# TSOC_PSoC4L.net
KiCad netlist of a schematic drawn in EAGLE
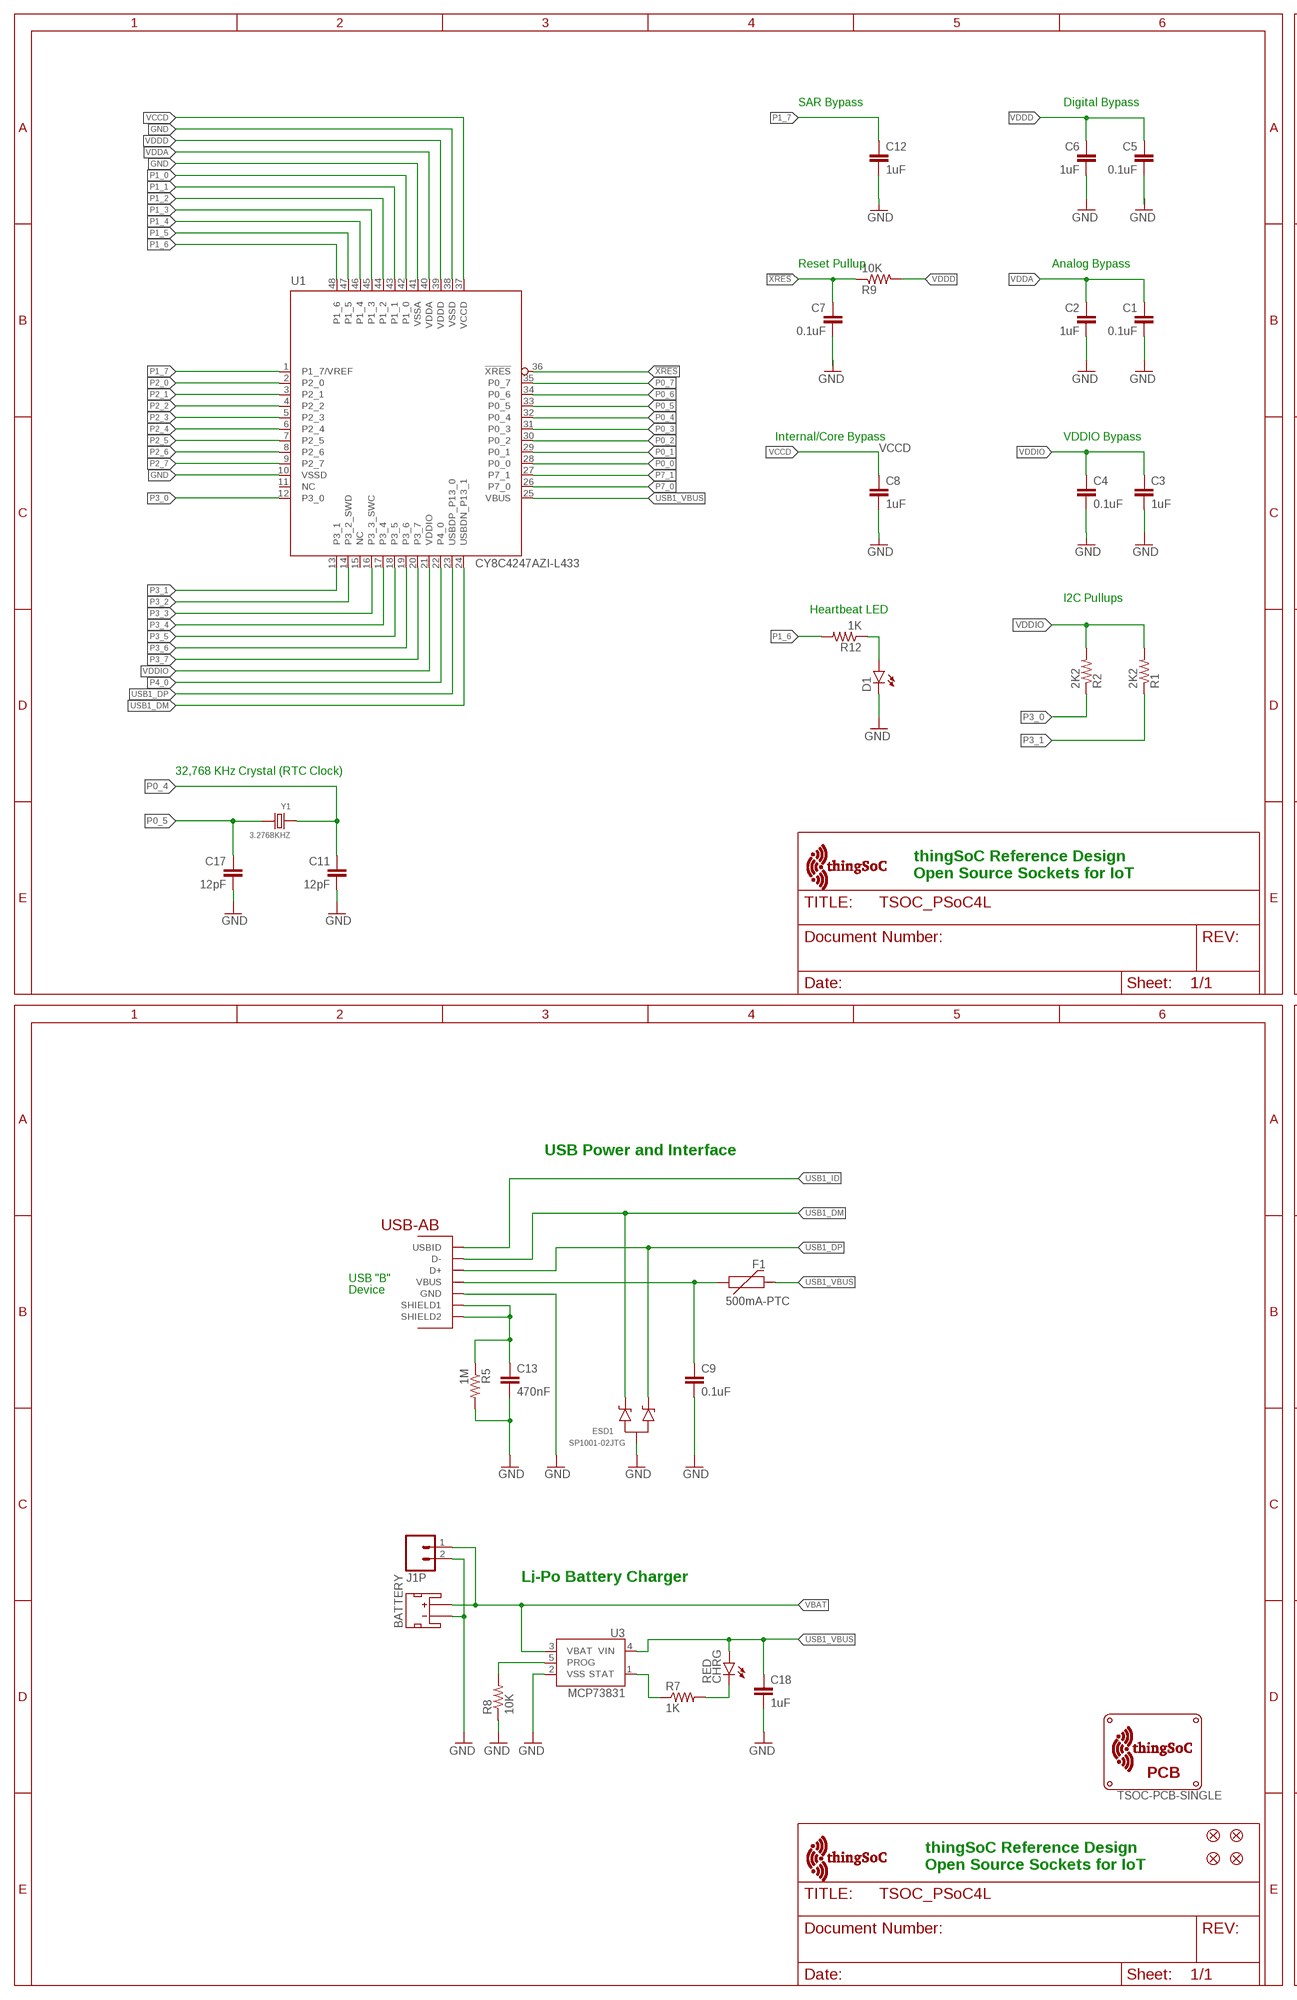
[diagram p0: schematic, sheet 1, part 1 of 2]
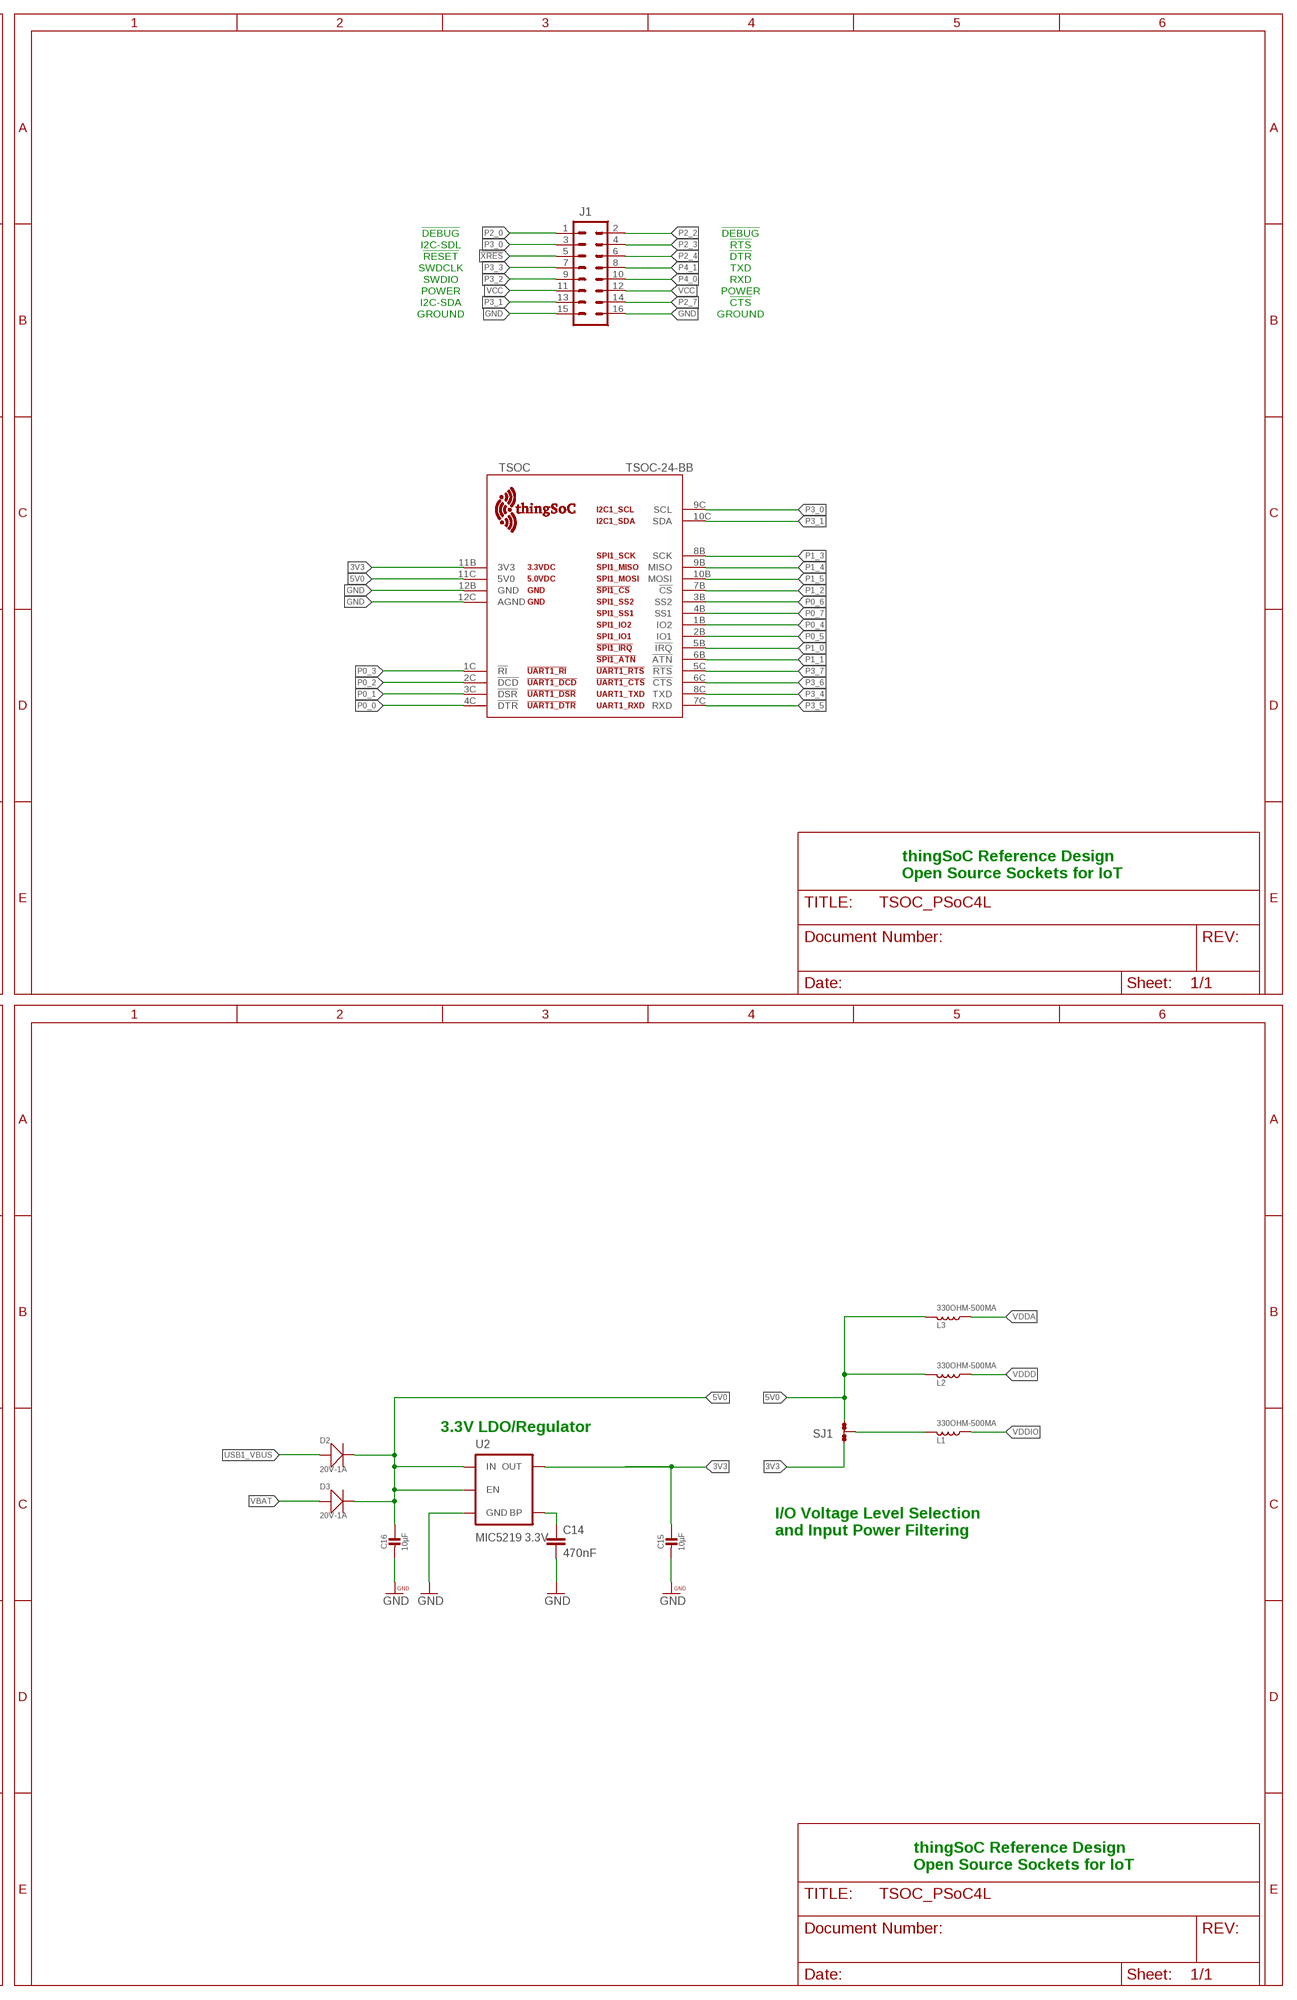
[diagram p1: schematic, sheet 1, part 2 of 2]

(export (version "E")
  (design (tool "Eeschema 10.0.6"))
  (components
    (comp (ref "BATTERY")
      (value "JST_2MM_MALE")
      (footprint "eagle-import:JST-2-SMD")
      (libsource (lib "eagle-import") (part "JST_2MM_MALE"))
    )
    (comp (ref "C1")
      (value "0.1uF")
      (footprint "eagle-import:0603-CAP")
      (libsource (lib "eagle-import") (part "CAP0603-CAP"))
    )
    (comp (ref "C2")
      (value "1uF")
      (footprint "eagle-import:0603-CAP")
      (libsource (lib "eagle-import") (part "CAP0603-CAP"))
    )
    (comp (ref "C3")
      (value "1uF")
      (footprint "eagle-import:0603-CAP")
      (libsource (lib "eagle-import") (part "CAP0603-CAP"))
    )
    (comp (ref "C4")
      (value "0.1uF")
      (footprint "eagle-import:0603-CAP")
      (libsource (lib "eagle-import") (part "CAP0603-CAP"))
    )
    (comp (ref "C5")
      (value "0.1uF")
      (footprint "eagle-import:0603-CAP")
      (libsource (lib "eagle-import") (part "CAP0603-CAP"))
    )
    (comp (ref "C6")
      (value "1uF")
      (footprint "eagle-import:0603-CAP")
      (libsource (lib "eagle-import") (part "CAP0603-CAP"))
    )
    (comp (ref "C7")
      (value "0.1uF")
      (footprint "eagle-import:0603-CAP")
      (libsource (lib "eagle-import") (part "CAP0603-CAP"))
    )
    (comp (ref "C8")
      (value "1uF")
      (footprint "eagle-import:0603-CAP")
      (libsource (lib "eagle-import") (part "CAP0603-CAP"))
    )
    (comp (ref "C9")
      (value "0.1uF")
      (footprint "eagle-import:0402-CAP")
      (libsource (lib "eagle-import") (part "TSOC-ESP8266-BASE_CAP0402-CAP"))
    )
    (comp (ref "C11")
      (value "12pF")
      (footprint "eagle-import:0603-CAP")
      (libsource (lib "eagle-import") (part "CAP0603-CAP"))
    )
    (comp (ref "C12")
      (value "1uF")
      (footprint "eagle-import:0603-CAP")
      (libsource (lib "eagle-import") (part "CAP0603-CAP"))
    )
    (comp (ref "C13")
      (value "470nF")
      (footprint "eagle-import:0402-CAP")
      (libsource (lib "eagle-import") (part "TSOC-ESP8266-BASE_CAP0402-CAP"))
    )
    (comp (ref "C14")
      (value "470nF")
      (footprint "eagle-import:0402-CAP")
      (libsource (lib "eagle-import") (part "TSOC-ESP8266-BASE_CAP0402-CAP"))
    )
    (comp (ref "C15")
      (value "10µF")
      (footprint "eagle-import:0805-NO")
      (libsource (lib "eagle-import") (part "CAP_CERAMIC0805-NOOUTLINE"))
    )
    (comp (ref "C16")
      (value "10µF")
      (footprint "eagle-import:0805-NO")
      (libsource (lib "eagle-import") (part "CAP_CERAMIC0805-NOOUTLINE"))
    )
    (comp (ref "C17")
      (value "12pF")
      (footprint "eagle-import:0603-CAP")
      (libsource (lib "eagle-import") (part "CAP0603-CAP"))
    )
    (comp (ref "C18")
      (value "1uF")
      (footprint "eagle-import:0603-CAP")
      (libsource (lib "eagle-import") (part "CAP0603-CAP"))
    )
    (comp (ref "CHRG")
      (value "RED")
      (footprint "eagle-import:LED-0603")
      (libsource (lib "eagle-import") (part "LED0603"))
    )
    (comp (ref "D1")
      (value "LED0603")
      (footprint "eagle-import:LED-0603")
      (libsource (lib "eagle-import") (part "LED0603"))
    )
    (comp (ref "D2")
      (value "20V-1A")
      (footprint "eagle-import:SOD-123")
      (fields (field (name "MPN") "B5819W"))
      (libsource (lib "eagle-import") (part "SMD-DIODE-SCHOTTKY-20V-1A(SOD-123)"))
    )
    (comp (ref "D3")
      (value "20V-1A")
      (footprint "eagle-import:SOD-123")
      (fields (field (name "MPN") "B5819W"))
      (libsource (lib "eagle-import") (part "SMD-DIODE-SCHOTTKY-20V-1A(SOD-123)"))
    )
    (comp (ref "ESD1")
      (value "SP1001-02JTG")
      (footprint "eagle-import:SC70-3")
      (libsource (lib "eagle-import") (part "SP1001-02JTG"))
    )
    (comp (ref "F1")
      (value "500mA-PTC")
      (footprint "eagle-import:PTC-1206")
      (libsource (lib "eagle-import") (part "PTCSMD"))
    )
    (comp (ref "FID1")
      (value "FIDUCIALUFIDUCIAL")
      (footprint "eagle-import:MICRO-FIDUCIAL")
      (libsource (lib "eagle-import") (part "FIDUCIALUFIDUCIAL"))
    )
    (comp (ref "FID2")
      (value "FIDUCIALUFIDUCIAL")
      (footprint "eagle-import:MICRO-FIDUCIAL")
      (libsource (lib "eagle-import") (part "FIDUCIALUFIDUCIAL"))
    )
    (comp (ref "FID3")
      (value "FIDUCIALUFIDUCIAL")
      (footprint "eagle-import:MICRO-FIDUCIAL")
      (libsource (lib "eagle-import") (part "FIDUCIALUFIDUCIAL"))
    )
    (comp (ref "FID4")
      (value "FIDUCIALUFIDUCIAL")
      (footprint "eagle-import:MICRO-FIDUCIAL")
      (libsource (lib "eagle-import") (part "FIDUCIALUFIDUCIAL"))
    )
    (comp (ref "J1")
      (value "M08X2")
      (footprint "eagle-import:2X8")
      (libsource (lib "eagle-import") (part "M08X2"))
    )
    (comp (ref "J1P")
      (value "M02-JST-2-PTH-NO_SILK")
      (footprint "eagle-import:JST-2-PTH-NS")
      (libsource (lib "eagle-import") (part "M02-JST-2-PTH-NO_SILK"))
    )
    (comp (ref "L1")
      (value "330OHM-500MA")
      (footprint "eagle-import:L0603")
      (fields (field (name "MPN") "BLM18AG121SN1D"))
      (libsource (lib "eagle-import") (part "SMD-FERRITE-CHIP-120-OHM-500MA(0603)"))
    )
    (comp (ref "L2")
      (value "330OHM-500MA")
      (footprint "eagle-import:L0603")
      (fields (field (name "MPN") "BLM18AG121SN1D"))
      (libsource (lib "eagle-import") (part "SMD-FERRITE-CHIP-120-OHM-500MA(0603)"))
    )
    (comp (ref "L3")
      (value "330OHM-500MA")
      (footprint "eagle-import:L0603")
      (fields (field (name "MPN") "BLM18AG121SN1D"))
      (libsource (lib "eagle-import") (part "SMD-FERRITE-CHIP-120-OHM-500MA(0603)"))
    )
    (comp (ref "R1")
      (value "2K2")
      (footprint "eagle-import:0603-RES")
      (libsource (lib "eagle-import") (part "RESISTOR_SFE0603-RES"))
    )
    (comp (ref "R2")
      (value "2K2")
      (footprint "eagle-import:0603-RES")
      (libsource (lib "eagle-import") (part "RESISTOR_SFE0603-RES"))
    )
    (comp (ref "R5")
      (value "1M")
      (footprint "eagle-import:0402-RES")
      (libsource (lib "eagle-import") (part "RESISTOR0402"))
    )
    (comp (ref "R7")
      (value "1K")
      (footprint "eagle-import:0402-RES")
      (libsource (lib "eagle-import") (part "RESISTOR0402"))
    )
    (comp (ref "R8")
      (value "10K")
      (footprint "eagle-import:0402-RES")
      (libsource (lib "eagle-import") (part "RESISTOR0402"))
    )
    (comp (ref "R9")
      (value "10K")
      (footprint "eagle-import:0603-RES")
      (libsource (lib "eagle-import") (part "RESISTOR_SFE0603-RES"))
    )
    (comp (ref "R12")
      (value "1K")
      (footprint "eagle-import:0603-RES")
      (libsource (lib "eagle-import") (part "RESISTOR_SFE0603-RES"))
    )
    (comp (ref "SJ1")
      (value "JMP-3-NC")
      (footprint "eagle-import:JMP-3-NC")
      (libsource (lib "eagle-import") (part "JMP-3-NC"))
    )
    (comp (ref "TSOC")
      (value "TSOC-24-BB")
      (footprint "eagle-import:TSOC-BB-S24")
      (libsource (lib "eagle-import") (part "TSOC-24-BB"))
    )
    (comp (ref "U$1")
      (value "TSOC-PCB-SINGLE")
      (footprint "eagle-import:TSOC-BB-BRD-DIM")
      (libsource (lib "eagle-import") (part "TSOC-PCB-SINGLE"))
    )
    (comp (ref "U$100")
      (value "TSOC-LOGO-SMALL")
      (footprint "eagle-import:TSOC-LOGO-SML")
      (libsource (lib "eagle-import") (part "TSOC-LOGO-SMALL"))
    )
    (comp (ref "U$101")
      (value "TSOC-LOGO-LRG")
      (footprint "eagle-import:TSOC-LOGO-LRG")
      (libsource (lib "eagle-import") (part "TSOC-LOGO-LRG"))
    )
    (comp (ref "U1")
      (value "CY8C4247AZI-L433")
      (footprint "eagle-import:TQFP-7X7-48")
      (libsource (lib "eagle-import") (part "CY8C4247AZI-L433"))
    )
    (comp (ref "U2")
      (value "MIC5219 3.3V")
      (footprint "eagle-import:SOT23-5")
      (libsource (lib "eagle-import") (part "V_REG_MIC52193.3V"))
    )
    (comp (ref "U3")
      (value "MCP73831")
      (footprint "eagle-import:SOT23-5")
      (libsource (lib "eagle-import") (part "MCP73831"))
    )
    (comp (ref "USB")
      (value "USB_AB")
      (footprint "eagle-import:USB-AB-MICRO-SMD")
      (libsource (lib "eagle-import") (part "USB_AB"))
    )
    (comp (ref "Y1")
      (value "3.2768KHZ")
      (footprint "eagle-import:X2-SMD-L2.0X1.2X0.55MM")
      (fields (field (name "MPN") "FC-12M"))
      (libsource (lib "eagle-import") (part "SMD-CRYSTAL-32.768KHZ-12.5PF-20PPM-90K(2P-L2.0X1.2MM)"))
    )
  )
  (nets
    (net (code "1") (name "/~{XRES}") (class "Default")
      (node (ref "C7") (pin "1") (pinfunction "1_1") (pintype "passive"))
      (node (ref "J1") (pin "5") (pinfunction "5_5") (pintype "passive"))
      (node (ref "R9") (pin "1") (pinfunction "1_1") (pintype "passive"))
      (node (ref "U1") (pin "36") (pinfunction "~{XRES}_36") (pintype "bidirectional"))
    )
    (net (code "2") (name "3V3") (class "Default")
      (node (ref "C15") (pin "1") (pinfunction "1_1") (pintype "passive"))
      (node (ref "SJ1") (pin "1") (pinfunction "1_1") (pintype "passive"))
      (node (ref "TSOC") (pin "11B") (pinfunction "3V3_11B") (pintype "bidirectional"))
      (node (ref "U2") (pin "5") (pinfunction "OUT_5") (pintype "passive"))
    )
    (net (code "3") (name "5V0") (class "Default")
      (node (ref "C16") (pin "1") (pinfunction "1_1") (pintype "passive"))
      (node (ref "D2") (pin "-") (pinfunction "-_-") (pintype "passive"))
      (node (ref "D3") (pin "-") (pinfunction "-_-") (pintype "passive"))
      (node (ref "L2") (pin "1") (pinfunction "1_1") (pintype "passive"))
      (node (ref "L3") (pin "1") (pinfunction "1_1") (pintype "passive"))
      (node (ref "SJ1") (pin "3") (pinfunction "3_3") (pintype "passive"))
      (node (ref "TSOC") (pin "11C") (pinfunction "5V0_11C") (pintype "bidirectional"))
      (node (ref "U2") (pin "1") (pinfunction "IN_1") (pintype "input"))
      (node (ref "U2") (pin "3") (pinfunction "EN_3") (pintype "input"))
    )
    (net (code "4") (name "GND") (class "Default")
      (node (ref "BATTERY") (pin "1") (pinfunction "-_1") (pintype "bidirectional"))
      (node (ref "C1") (pin "2") (pinfunction "2_2") (pintype "passive"))
      (node (ref "C11") (pin "2") (pinfunction "2_2") (pintype "passive"))
      (node (ref "C12") (pin "2") (pinfunction "2_2") (pintype "passive"))
      (node (ref "C13") (pin "2") (pinfunction "2_2") (pintype "passive"))
      (node (ref "C14") (pin "2") (pinfunction "2_2") (pintype "passive"))
      (node (ref "C15") (pin "2") (pinfunction "2_2") (pintype "passive"))
      (node (ref "C16") (pin "2") (pinfunction "2_2") (pintype "passive"))
      (node (ref "C17") (pin "2") (pinfunction "2_2") (pintype "passive"))
      (node (ref "C18") (pin "2") (pinfunction "2_2") (pintype "passive"))
      (node (ref "C2") (pin "2") (pinfunction "2_2") (pintype "passive"))
      (node (ref "C3") (pin "2") (pinfunction "2_2") (pintype "passive"))
      (node (ref "C4") (pin "2") (pinfunction "2_2") (pintype "passive"))
      (node (ref "C5") (pin "2") (pinfunction "2_2") (pintype "passive"))
      (node (ref "C6") (pin "2") (pinfunction "2_2") (pintype "passive"))
      (node (ref "C7") (pin "2") (pinfunction "2_2") (pintype "passive"))
      (node (ref "C8") (pin "2") (pinfunction "2_2") (pintype "passive"))
      (node (ref "C9") (pin "2") (pinfunction "2_2") (pintype "passive"))
      (node (ref "D1") (pin "C") (pinfunction "C_C") (pintype "passive"))
      (node (ref "ESD1") (pin "3") (pinfunction "A_3") (pintype "passive"))
      (node (ref "J1") (pin "15") (pinfunction "15_15") (pintype "passive"))
      (node (ref "J1") (pin "16") (pinfunction "16_16") (pintype "passive"))
      (node (ref "J1P") (pin "2") (pinfunction "2_2") (pintype "passive"))
      (node (ref "R5") (pin "2") (pinfunction "2_2") (pintype "passive"))
      (node (ref "R8") (pin "1") (pinfunction "1_1") (pintype "passive"))
      (node (ref "TSOC") (pin "12B") (pinfunction "GND_12B") (pintype "bidirectional"))
      (node (ref "TSOC") (pin "12C") (pinfunction "AGND_12C") (pintype "bidirectional"))
      (node (ref "U1") (pin "10") (pinfunction "VSSD_10") (pintype "bidirectional"))
      (node (ref "U1") (pin "38") (pinfunction "VSSD_38") (pintype "bidirectional"))
      (node (ref "U1") (pin "41") (pinfunction "VSSA_41") (pintype "bidirectional"))
      (node (ref "U2") (pin "2") (pinfunction "GND_2") (pintype "input"))
      (node (ref "U3") (pin "2") (pinfunction "VSS_2") (pintype "power_in"))
      (node (ref "USB") (pin "GND") (pinfunction "GND_GND") (pintype "bidirectional"))
    )
    (net (code "5") (name "Net-(C9-Pad1)") (class "Default")
      (node (ref "C9") (pin "1") (pinfunction "1_1") (pintype "passive"))
      (node (ref "F1") (pin "1") (pinfunction "1_1") (pintype "bidirectional"))
      (node (ref "USB") (pin "VBUS") (pinfunction "VBUS_VBUS") (pintype "bidirectional"))
    )
    (net (code "6") (name "Net-(C13-Pad1)") (class "Default")
      (node (ref "C13") (pin "1") (pinfunction "1_1") (pintype "passive"))
      (node (ref "R5") (pin "1") (pinfunction "1_1") (pintype "passive"))
      (node (ref "USB") (pin "SHIELD1") (pinfunction "SHIELD1_SHIELD1") (pintype "bidirectional"))
      (node (ref "USB") (pin "SHIELD2") (pinfunction "SHIELD2_SHIELD2") (pintype "bidirectional"))
    )
    (net (code "7") (name "Net-(CHRG-PadC)") (class "Default")
      (node (ref "CHRG") (pin "C") (pinfunction "C_C") (pintype "passive"))
      (node (ref "R7") (pin "2") (pinfunction "2_2") (pintype "passive"))
    )
    (net (code "8") (name "Net-(D1-PadA)") (class "Default")
      (node (ref "D1") (pin "A") (pinfunction "A_A") (pintype "passive"))
      (node (ref "R12") (pin "1") (pinfunction "1_1") (pintype "passive"))
    )
    (net (code "9") (name "Net-(L1-Pad1)") (class "Default")
      (node (ref "L1") (pin "1") (pinfunction "1_1") (pintype "passive"))
      (node (ref "SJ1") (pin "2") (pinfunction "2_2") (pintype "passive"))
    )
    (net (code "10") (name "Net-(U2-BP)") (class "Default")
      (node (ref "C14") (pin "1") (pinfunction "1_1") (pintype "passive"))
      (node (ref "U2") (pin "4") (pinfunction "BP_4") (pintype "input"))
    )
    (net (code "11") (name "Net-(U3-PROG)") (class "Default")
      (node (ref "R8") (pin "2") (pinfunction "2_2") (pintype "passive"))
      (node (ref "U3") (pin "5") (pinfunction "PROG_5") (pintype "input"))
    )
    (net (code "12") (name "Net-(U3-STAT)") (class "Default")
      (node (ref "R7") (pin "1") (pinfunction "1_1") (pintype "passive"))
      (node (ref "U3") (pin "1") (pinfunction "STAT_1") (pintype "output"))
    )
    (net (code "13") (name "P0_0") (class "Default")
      (node (ref "TSOC") (pin "4C") (pinfunction "~{DTR}_4C") (pintype "bidirectional"))
      (node (ref "U1") (pin "28") (pinfunction "P0_0_28") (pintype "bidirectional"))
    )
    (net (code "14") (name "P0_1") (class "Default")
      (node (ref "TSOC") (pin "3C") (pinfunction "~{DSR}_3C") (pintype "bidirectional"))
      (node (ref "U1") (pin "29") (pinfunction "P0_1_29") (pintype "bidirectional"))
    )
    (net (code "15") (name "P0_2") (class "Default")
      (node (ref "TSOC") (pin "2C") (pinfunction "~{DCD}_2C") (pintype "bidirectional"))
      (node (ref "U1") (pin "30") (pinfunction "P0_2_30") (pintype "input"))
    )
    (net (code "16") (name "P0_3") (class "Default")
      (node (ref "TSOC") (pin "1C") (pinfunction "~{RI}_1C") (pintype "bidirectional"))
      (node (ref "U1") (pin "31") (pinfunction "P0_3_31") (pintype "bidirectional"))
    )
    (net (code "17") (name "P0_4") (class "Default")
      (node (ref "C11") (pin "1") (pinfunction "1_1") (pintype "passive"))
      (node (ref "TSOC") (pin "1B") (pinfunction "IO2_1B") (pintype "bidirectional"))
      (node (ref "U1") (pin "32") (pinfunction "P0_4_32") (pintype "bidirectional"))
      (node (ref "Y1") (pin "1") (pinfunction "1_1") (pintype "passive"))
    )
    (net (code "18") (name "P0_5") (class "Default")
      (node (ref "C17") (pin "1") (pinfunction "1_1") (pintype "passive"))
      (node (ref "TSOC") (pin "2B") (pinfunction "IO1_2B") (pintype "bidirectional"))
      (node (ref "U1") (pin "33") (pinfunction "P0_5_33") (pintype "bidirectional"))
      (node (ref "Y1") (pin "2") (pinfunction "2_2") (pintype "passive"))
    )
    (net (code "19") (name "P0_6") (class "Default")
      (node (ref "TSOC") (pin "3B") (pinfunction "SS2_3B") (pintype "bidirectional"))
      (node (ref "U1") (pin "34") (pinfunction "P0_6_34") (pintype "power_in"))
    )
    (net (code "20") (name "P0_7") (class "Default")
      (node (ref "TSOC") (pin "4B") (pinfunction "SS1_4B") (pintype "bidirectional"))
      (node (ref "U1") (pin "35") (pinfunction "P0_7_35") (pintype "bidirectional"))
    )
    (net (code "21") (name "P1_0") (class "Default")
      (node (ref "TSOC") (pin "5B") (pinfunction "~{IRQ}_5B") (pintype "bidirectional"))
      (node (ref "U1") (pin "42") (pinfunction "P1_0_42") (pintype "bidirectional"))
    )
    (net (code "22") (name "P1_1") (class "Default")
      (node (ref "TSOC") (pin "6B") (pinfunction "~{ATN}_6B") (pintype "bidirectional"))
      (node (ref "U1") (pin "43") (pinfunction "P1_1_43") (pintype "bidirectional"))
    )
    (net (code "23") (name "P1_2") (class "Default")
      (node (ref "TSOC") (pin "7B") (pinfunction "~{CS}_7B") (pintype "bidirectional"))
      (node (ref "U1") (pin "44") (pinfunction "P1_2_44") (pintype "power_in"))
    )
    (net (code "24") (name "P1_3") (class "Default")
      (node (ref "TSOC") (pin "8B") (pinfunction "SCK_8B") (pintype "bidirectional"))
      (node (ref "U1") (pin "45") (pinfunction "P1_3_45") (pintype "bidirectional"))
    )
    (net (code "25") (name "P1_4") (class "Default")
      (node (ref "TSOC") (pin "9B") (pinfunction "MISO_9B") (pintype "bidirectional"))
      (node (ref "U1") (pin "46") (pinfunction "P1_4_46") (pintype "bidirectional"))
    )
    (net (code "26") (name "P1_5") (class "Default")
      (node (ref "TSOC") (pin "10B") (pinfunction "MOSI_10B") (pintype "bidirectional"))
      (node (ref "U1") (pin "47") (pinfunction "P1_5_47") (pintype "bidirectional"))
    )
    (net (code "27") (name "P1_6") (class "Default")
      (node (ref "R12") (pin "2") (pinfunction "2_2") (pintype "passive"))
      (node (ref "U1") (pin "48") (pinfunction "P1_6_48") (pintype "bidirectional"))
    )
    (net (code "28") (name "P1_7") (class "Default")
      (node (ref "C12") (pin "1") (pinfunction "1_1") (pintype "passive"))
      (node (ref "U1") (pin "1") (pinfunction "P1_7/VREF_1") (pintype "bidirectional"))
    )
    (net (code "29") (name "P2_0") (class "Default")
      (node (ref "J1") (pin "1") (pinfunction "1_1") (pintype "passive"))
      (node (ref "U1") (pin "2") (pinfunction "P2_0_2") (pintype "bidirectional"))
    )
    (net (code "30") (name "P2_1") (class "Default")
      (node (ref "U1") (pin "3") (pinfunction "P2_1_3") (pintype "bidirectional"))
    )
    (net (code "31") (name "P2_2") (class "Default")
      (node (ref "J1") (pin "2") (pinfunction "2_2") (pintype "passive"))
      (node (ref "U1") (pin "4") (pinfunction "P2_2_4") (pintype "power_in"))
    )
    (net (code "32") (name "P2_3") (class "Default")
      (node (ref "J1") (pin "4") (pinfunction "4_4") (pintype "passive"))
      (node (ref "U1") (pin "5") (pinfunction "P2_3_5") (pintype "bidirectional"))
    )
    (net (code "33") (name "P2_4") (class "Default")
      (node (ref "J1") (pin "6") (pinfunction "6_6") (pintype "passive"))
      (node (ref "U1") (pin "6") (pinfunction "P2_4_6") (pintype "bidirectional"))
    )
    (net (code "34") (name "P2_5") (class "Default")
      (node (ref "U1") (pin "7") (pinfunction "P2_5_7") (pintype "bidirectional"))
    )
    (net (code "35") (name "P2_6") (class "Default")
      (node (ref "U1") (pin "8") (pinfunction "P2_6_8") (pintype "power_in"))
    )
    (net (code "36") (name "P2_7") (class "Default")
      (node (ref "J1") (pin "14") (pinfunction "14_14") (pintype "passive"))
      (node (ref "U1") (pin "9") (pinfunction "P2_7_9") (pintype "bidirectional"))
    )
    (net (code "37") (name "P3_0") (class "Default")
      (node (ref "J1") (pin "3") (pinfunction "3_3") (pintype "passive"))
      (node (ref "R2") (pin "1") (pinfunction "1_1") (pintype "passive"))
      (node (ref "TSOC") (pin "9C") (pinfunction "SCL_9C") (pintype "bidirectional"))
      (node (ref "U1") (pin "12") (pinfunction "P3_0_12") (pintype "bidirectional"))
    )
    (net (code "38") (name "P3_1") (class "Default")
      (node (ref "J1") (pin "13") (pinfunction "13_13") (pintype "passive"))
      (node (ref "R1") (pin "1") (pinfunction "1_1") (pintype "passive"))
      (node (ref "TSOC") (pin "10C") (pinfunction "SDA_10C") (pintype "bidirectional"))
      (node (ref "U1") (pin "13") (pinfunction "P3_1_13") (pintype "bidirectional"))
    )
    (net (code "39") (name "P3_2") (class "Default")
      (node (ref "J1") (pin "9") (pinfunction "9_9") (pintype "passive"))
      (node (ref "U1") (pin "14") (pinfunction "P3_2_SWD_14") (pintype "bidirectional"))
    )
    (net (code "40") (name "P3_3") (class "Default")
      (node (ref "J1") (pin "7") (pinfunction "7_7") (pintype "passive"))
      (node (ref "U1") (pin "16") (pinfunction "P3_3_SWC_16") (pintype "bidirectional"))
    )
    (net (code "41") (name "P3_4") (class "Default")
      (node (ref "TSOC") (pin "8C") (pinfunction "TXD_8C") (pintype "bidirectional"))
      (node (ref "U1") (pin "17") (pinfunction "P3_4_17") (pintype "bidirectional"))
    )
    (net (code "42") (name "P3_5") (class "Default")
      (node (ref "TSOC") (pin "7C") (pinfunction "RXD_7C") (pintype "bidirectional"))
      (node (ref "U1") (pin "18") (pinfunction "P3_5_18") (pintype "bidirectional"))
    )
    (net (code "43") (name "P3_6") (class "Default")
      (node (ref "TSOC") (pin "6C") (pinfunction "~{CTS}_6C") (pintype "bidirectional"))
      (node (ref "U1") (pin "19") (pinfunction "P3_6_19") (pintype "power_in"))
    )
    (net (code "44") (name "P3_7") (class "Default")
      (node (ref "TSOC") (pin "5C") (pinfunction "~{RTS}_5C") (pintype "bidirectional"))
      (node (ref "U1") (pin "20") (pinfunction "P3_7_20") (pintype "bidirectional"))
    )
    (net (code "45") (name "P4_0") (class "Default")
      (node (ref "J1") (pin "10") (pinfunction "10_10") (pintype "passive"))
      (node (ref "U1") (pin "22") (pinfunction "P4_0_22") (pintype "bidirectional"))
    )
    (net (code "46") (name "P4_1") (class "Default")
      (node (ref "J1") (pin "8") (pinfunction "8_8") (pintype "passive"))
    )
    (net (code "47") (name "P7_0") (class "Default")
      (node (ref "U1") (pin "26") (pinfunction "P7_0_26") (pintype "bidirectional"))
    )
    (net (code "48") (name "P7_1") (class "Default")
      (node (ref "U1") (pin "27") (pinfunction "P7_1_27") (pintype "bidirectional"))
    )
    (net (code "49") (name "USB1_DM") (class "Default")
      (node (ref "ESD1") (pin "2") (pinfunction "C2_2") (pintype "passive"))
      (node (ref "U1") (pin "24") (pinfunction "USBDN_P13_1_24") (pintype "bidirectional"))
      (node (ref "USB") (pin "D-") (pinfunction "D-_D-") (pintype "bidirectional"))
    )
    (net (code "50") (name "USB1_DP") (class "Default")
      (node (ref "ESD1") (pin "1") (pinfunction "C1_1") (pintype "passive"))
      (node (ref "U1") (pin "23") (pinfunction "USBDP_P13_0_23") (pintype "bidirectional"))
      (node (ref "USB") (pin "D+") (pinfunction "D+_D+") (pintype "bidirectional"))
    )
    (net (code "51") (name "USB1_ID") (class "Default")
      (node (ref "USB") (pin "ID") (pinfunction "USBID_ID") (pintype "bidirectional"))
    )
    (net (code "52") (name "USB1_VBUS") (class "Default")
      (node (ref "C18") (pin "1") (pinfunction "1_1") (pintype "passive"))
      (node (ref "CHRG") (pin "A") (pinfunction "A_A") (pintype "passive"))
      (node (ref "D2") (pin "+") (pinfunction "+_+") (pintype "passive"))
      (node (ref "F1") (pin "2") (pinfunction "2_2") (pintype "bidirectional"))
      (node (ref "U1") (pin "25") (pinfunction "VBUS_25") (pintype "bidirectional"))
      (node (ref "U3") (pin "4") (pinfunction "VIN_4") (pintype "power_in"))
    )
    (net (code "53") (name "VBAT") (class "Default")
      (node (ref "BATTERY") (pin "2") (pinfunction "+_2") (pintype "bidirectional"))
      (node (ref "D3") (pin "+") (pinfunction "+_+") (pintype "passive"))
      (node (ref "J1P") (pin "1") (pinfunction "1_1") (pintype "passive"))
      (node (ref "U3") (pin "3") (pinfunction "VBAT_3") (pintype "power_in"))
    )
    (net (code "54") (name "VCC") (class "Default")
      (node (ref "J1") (pin "11") (pinfunction "11_11") (pintype "passive"))
      (node (ref "J1") (pin "12") (pinfunction "12_12") (pintype "passive"))
    )
    (net (code "55") (name "VCCD") (class "Default")
      (node (ref "C8") (pin "1") (pinfunction "1_1") (pintype "passive"))
      (node (ref "U1") (pin "37") (pinfunction "VCCD_37") (pintype "bidirectional"))
    )
    (net (code "56") (name "VDDA") (class "Default")
      (node (ref "C1") (pin "1") (pinfunction "1_1") (pintype "passive"))
      (node (ref "C2") (pin "1") (pinfunction "1_1") (pintype "passive"))
      (node (ref "L3") (pin "2") (pinfunction "2_2") (pintype "passive"))
      (node (ref "U1") (pin "40") (pinfunction "VDDA_40") (pintype "bidirectional"))
    )
    (net (code "57") (name "VDDD") (class "Default")
      (node (ref "C5") (pin "1") (pinfunction "1_1") (pintype "passive"))
      (node (ref "C6") (pin "1") (pinfunction "1_1") (pintype "passive"))
      (node (ref "L2") (pin "2") (pinfunction "2_2") (pintype "passive"))
      (node (ref "R9") (pin "2") (pinfunction "2_2") (pintype "passive"))
      (node (ref "U1") (pin "39") (pinfunction "VDDD_39") (pintype "bidirectional"))
    )
    (net (code "58") (name "VDDIO") (class "Default")
      (node (ref "C3") (pin "1") (pinfunction "1_1") (pintype "passive"))
      (node (ref "C4") (pin "1") (pinfunction "1_1") (pintype "passive"))
      (node (ref "L1") (pin "2") (pinfunction "2_2") (pintype "passive"))
      (node (ref "R1") (pin "2") (pinfunction "2_2") (pintype "passive"))
      (node (ref "R2") (pin "2") (pinfunction "2_2") (pintype "passive"))
      (node (ref "U1") (pin "21") (pinfunction "VDDIO_21") (pintype "bidirectional"))
    )
    (net (code "59") (name "unconnected-(BATTERY-PAD1-PadNC1)") (class "Default")
      (node (ref "BATTERY") (pin "NC1") (pinfunction "PAD1_NC1") (pintype "bidirectional"))
    )
    (net (code "60") (name "unconnected-(BATTERY-PAD2-PadNC2)") (class "Default")
      (node (ref "BATTERY") (pin "NC2") (pinfunction "PAD2_NC2") (pintype "bidirectional"))
    )
    (net (code "61") (name "unconnected-(U1-NC-Pad11)") (class "Default")
      (node (ref "U1") (pin "11") (pinfunction "NC_11") (pintype "bidirectional"))
    )
    (net (code "62") (name "unconnected-(U1-NC-Pad15)") (class "Default")
      (node (ref "U1") (pin "15") (pinfunction "NC_15") (pintype "bidirectional"))
    )
  )
)
